# hbridge.net
KiCad netlist of a schematic drawn in Altium Designer
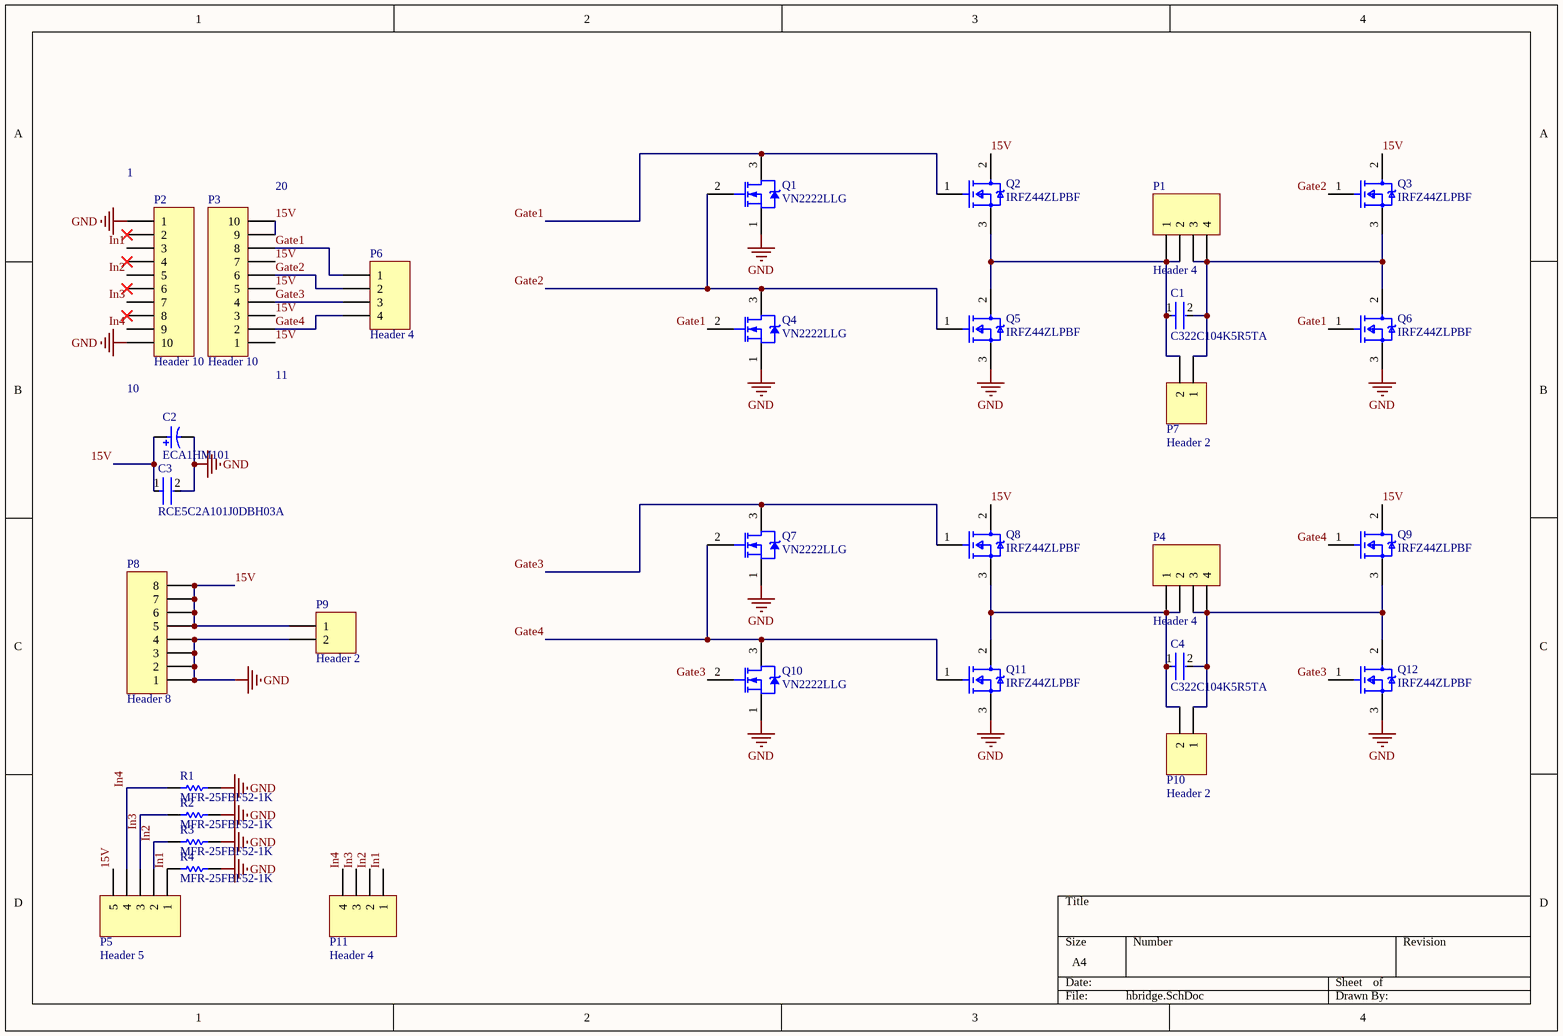
[diagram p0: hbridge.SchDoc]

(export (version "E")
  (design (tool "Eeschema 10.0.6"))
  (components
    (comp (ref "C1")
      (value "C322C104K5R5TA")
      (footprint "FP-C322C104K5R5TA-MFG")
      (description "CAP CER 0.1UF 50V X7R RADIAL")
      (fields (field (name "TOLERANCE") "10%") (field (name "VOLTAGE") "50V"))
      (libsource (lib "Altium Content Vault") (part "b4654b650e69147ec39a6b967a45e02"))
    )
    (comp (ref "C2")
      (value "ECA1HM101")
      (footprint "CAPPR65-350-1150X800X1250")
      (description "Aluminum Electrolytic Capacitor, 100 uF, +/- 20%, 50 V, -40 to 85 degC, 2-Pin THD, RoHS, Bulk")
      (fields (field (name "MANUFACTURER") "Panasonic") (field (name "VOLTAGE") "50V"))
      (libsource (lib "Altium Content Vault") (part "CAP-P-2"))
    )
    (comp (ref "C3")
      (value "RCE5C2A101J0DBH03A")
      (footprint "FP-RCE0DB-MFG")
      (description "Cap Ceramic 100pF 100V C0G ±5% Radial 2.5mm +125°C Ammo Pack")
      (fields (field (name "TOLERANCE") "5%"))
      (libsource (lib "Altium Content Vault") (part "b4654b650e69147ec39a6b967a45e02"))
    )
    (comp (ref "C4")
      (value "C322C104K5R5TA")
      (footprint "FP-C322C104K5R5TA-MFG")
      (description "CAP CER 0.1UF 50V X7R RADIAL")
      (fields (field (name "TOLERANCE") "10%") (field (name "VOLTAGE") "50V"))
      (libsource (lib "Altium Content Vault") (part "b4654b650e69147ec39a6b967a45e02"))
    )
    (comp (ref "P1")
      (value "Header 4")
      (footprint "HDR1X4")
      (description "Header, 4-Pin")
      (fields (field (name "PUBLISHER") "Altium Limited"))
      (libsource (lib "Miscellaneous Connectors") (part "Header 4"))
    )
    (comp (ref "P2")
      (value "Header 10")
      (footprint "HDR1X10")
      (description "Header, 10-Pin")
      (fields (field (name "PUBLISHER") "Altium Limited"))
      (libsource (lib "Miscellaneous Connectors") (part "Header 10"))
    )
    (comp (ref "P3")
      (value "Header 10")
      (footprint "HDR1X10")
      (description "Header, 10-Pin")
      (fields (field (name "PUBLISHER") "Altium Limited"))
      (libsource (lib "") (part "Header 10_1"))
    )
    (comp (ref "P4")
      (value "Header 4")
      (footprint "HDR1X4")
      (description "Header, 4-Pin")
      (fields (field (name "PUBLISHER") "Altium Limited"))
      (libsource (lib "Miscellaneous Connectors") (part "Header 4"))
    )
    (comp (ref "P5")
      (value "Header 5")
      (footprint "HDR1X5")
      (description "Header, 5-Pin")
      (fields (field (name "PUBLISHER") "Altium Limited"))
      (libsource (lib "Miscellaneous Connectors") (part "Header 5"))
    )
    (comp (ref "P6")
      (value "Header 4")
      (footprint "HDR1X4")
      (description "Header, 4-Pin")
      (fields (field (name "PUBLISHER") "Altium Limited"))
      (libsource (lib "") (part "Header 4_2"))
    )
    (comp (ref "P7")
      (value "Header 2")
      (footprint "HDR1X2")
      (description "Header, 2-Pin")
      (fields (field (name "PUBLISHER") "Altium Limited"))
      (libsource (lib "Miscellaneous Connectors") (part "Header 2"))
    )
    (comp (ref "P8")
      (value "Header 8")
      (footprint "HDR1X8")
      (description "Header, 8-Pin")
      (fields (field (name "PUBLISHER") "Altium Limited"))
      (libsource (lib "Miscellaneous Connectors") (part "Header 8"))
    )
    (comp (ref "P9")
      (value "Header 2")
      (footprint "HDR1X2")
      (description "Header, 2-Pin")
      (fields (field (name "PUBLISHER") "Altium Limited"))
      (libsource (lib "") (part "Header 2_1"))
    )
    (comp (ref "P10")
      (value "Header 2")
      (footprint "HDR1X2")
      (description "Header, 2-Pin")
      (fields (field (name "PUBLISHER") "Altium Limited"))
      (libsource (lib "Miscellaneous Connectors") (part "Header 2"))
    )
    (comp (ref "P11")
      (value "Header 4")
      (footprint "HDR1X4")
      (description "Header, 4-Pin")
      (fields (field (name "PUBLISHER") "Altium Limited"))
      (libsource (lib "") (part "Header 4_1"))
    )
    (comp (ref "Q1")
      (value "VN2222LLG")
      (footprint "ONSC-TO-92-3-29-11")
      (description "Small Signal MOSFET, 150 mA, 60 V, N-Channel, 3-Pin TO-92, Pb-Free, Bulk Box")
      (fields (field (name "MANUFACTURER") "On Semiconductor"))
      (libsource (lib "Altium Content Vault") (part "ONSC-NMOS-S1G2D3-3"))
    )
    (comp (ref "Q2")
      (value "IRFZ44ZLPBF")
      (footprint "FP-PG-TO262-3-MFG")
      (description "MOSFET N-CH 55V 51A TO262")
      (libsource (lib "Altium Content Vault") (part "b09f7f152735e370c1ea22a33fa83d6"))
    )
    (comp (ref "Q3")
      (value "IRFZ44ZLPBF")
      (footprint "FP-PG-TO262-3-MFG")
      (description "MOSFET N-CH 55V 51A TO262")
      (libsource (lib "Altium Content Vault") (part "b09f7f152735e370c1ea22a33fa83d6"))
    )
    (comp (ref "Q4")
      (value "VN2222LLG")
      (footprint "ONSC-TO-92-3-29-11")
      (description "Small Signal MOSFET, 150 mA, 60 V, N-Channel, 3-Pin TO-92, Pb-Free, Bulk Box")
      (fields (field (name "MANUFACTURER") "On Semiconductor"))
      (libsource (lib "Altium Content Vault") (part "ONSC-NMOS-S1G2D3-3"))
    )
    (comp (ref "Q5")
      (value "IRFZ44ZLPBF")
      (footprint "FP-PG-TO262-3-MFG")
      (description "MOSFET N-CH 55V 51A TO262")
      (libsource (lib "Altium Content Vault") (part "b09f7f152735e370c1ea22a33fa83d6"))
    )
    (comp (ref "Q6")
      (value "IRFZ44ZLPBF")
      (footprint "FP-PG-TO262-3-MFG")
      (description "MOSFET N-CH 55V 51A TO262")
      (libsource (lib "Altium Content Vault") (part "b09f7f152735e370c1ea22a33fa83d6"))
    )
    (comp (ref "Q7")
      (value "VN2222LLG")
      (footprint "ONSC-TO-92-3-29-11")
      (description "Small Signal MOSFET, 150 mA, 60 V, N-Channel, 3-Pin TO-92, Pb-Free, Bulk Box")
      (fields (field (name "MANUFACTURER") "On Semiconductor"))
      (libsource (lib "Altium Content Vault") (part "ONSC-NMOS-S1G2D3-3"))
    )
    (comp (ref "Q8")
      (value "IRFZ44ZLPBF")
      (footprint "FP-PG-TO262-3-MFG")
      (description "MOSFET N-CH 55V 51A TO262")
      (libsource (lib "Altium Content Vault") (part "b09f7f152735e370c1ea22a33fa83d6"))
    )
    (comp (ref "Q9")
      (value "IRFZ44ZLPBF")
      (footprint "FP-PG-TO262-3-MFG")
      (description "MOSFET N-CH 55V 51A TO262")
      (libsource (lib "Altium Content Vault") (part "b09f7f152735e370c1ea22a33fa83d6"))
    )
    (comp (ref "Q10")
      (value "VN2222LLG")
      (footprint "ONSC-TO-92-3-29-11")
      (description "Small Signal MOSFET, 150 mA, 60 V, N-Channel, 3-Pin TO-92, Pb-Free, Bulk Box")
      (fields (field (name "MANUFACTURER") "On Semiconductor"))
      (libsource (lib "Altium Content Vault") (part "ONSC-NMOS-S1G2D3-3"))
    )
    (comp (ref "Q11")
      (value "IRFZ44ZLPBF")
      (footprint "FP-PG-TO262-3-MFG")
      (description "MOSFET N-CH 55V 51A TO262")
      (libsource (lib "Altium Content Vault") (part "b09f7f152735e370c1ea22a33fa83d6"))
    )
    (comp (ref "Q12")
      (value "IRFZ44ZLPBF")
      (footprint "FP-PG-TO262-3-MFG")
      (description "MOSFET N-CH 55V 51A TO262")
      (libsource (lib "Altium Content Vault") (part "b09f7f152735e370c1ea22a33fa83d6"))
    )
    (comp (ref "R1")
      (value "MFR-25FBF52-1K")
      (footprint "RESA60-630X240")
      (description "Axial Resistor, 1 KOhm, +/- 1%, 250 mW, -55 to 155 degC, 2-Pin THD, RoHS, Bulk")
      (fields (field (name "TOLERANCE") "1%"))
      (libsource (lib "Altium Content Vault") (part "RES-2"))
    )
    (comp (ref "R2")
      (value "MFR-25FBF52-1K")
      (footprint "RESA60-630X240")
      (description "Axial Resistor, 1 KOhm, +/- 1%, 250 mW, -55 to 155 degC, 2-Pin THD, RoHS, Bulk")
      (fields (field (name "TOLERANCE") "1%"))
      (libsource (lib "Altium Content Vault") (part "RES-2"))
    )
    (comp (ref "R3")
      (value "MFR-25FBF52-1K")
      (footprint "RESA60-630X240")
      (description "Axial Resistor, 1 KOhm, +/- 1%, 250 mW, -55 to 155 degC, 2-Pin THD, RoHS, Bulk")
      (fields (field (name "TOLERANCE") "1%"))
      (libsource (lib "Altium Content Vault") (part "RES-2"))
    )
    (comp (ref "R4")
      (value "MFR-25FBF52-1K")
      (footprint "RESA60-630X240")
      (description "Axial Resistor, 1 KOhm, +/- 1%, 250 mW, -55 to 155 degC, 2-Pin THD, RoHS, Bulk")
      (fields (field (name "TOLERANCE") "1%"))
      (libsource (lib "Altium Content Vault") (part "RES-2"))
    )
  )
  (nets
    (net (code "1") (name "/15V") (class "Default")
      (node (ref "C2") (pin "1") (pinfunction "1_1") (pintype "passive"))
      (node (ref "C3") (pin "1") (pinfunction "1_1") (pintype "passive"))
      (node (ref "P3") (pin "1") (pinfunction "1_1") (pintype "passive"))
      (node (ref "P3") (pin "10") (pinfunction "10_10") (pintype "passive"))
      (node (ref "P3") (pin "3") (pinfunction "3_3") (pintype "passive"))
      (node (ref "P3") (pin "5") (pinfunction "5_5") (pintype "passive"))
      (node (ref "P3") (pin "7") (pinfunction "7_7") (pintype "passive"))
      (node (ref "P3") (pin "9") (pinfunction "9_9") (pintype "passive"))
      (node (ref "P5") (pin "5") (pinfunction "5_5") (pintype "passive"))
      (node (ref "P8") (pin "5") (pinfunction "5_5") (pintype "passive"))
      (node (ref "P8") (pin "6") (pinfunction "6_6") (pintype "passive"))
      (node (ref "P8") (pin "7") (pinfunction "7_7") (pintype "passive"))
      (node (ref "P8") (pin "8") (pinfunction "8_8") (pintype "passive"))
      (node (ref "P9") (pin "1") (pinfunction "1_1") (pintype "passive"))
      (node (ref "Q2") (pin "2") (pinfunction "D_2") (pintype "passive"))
      (node (ref "Q3") (pin "2") (pinfunction "D_2") (pintype "passive"))
      (node (ref "Q8") (pin "2") (pinfunction "D_2") (pintype "passive"))
      (node (ref "Q9") (pin "2") (pinfunction "D_2") (pintype "passive"))
    )
    (net (code "2") (name "/Gate1") (class "Default")
      (node (ref "P3") (pin "8") (pinfunction "8_8") (pintype "passive"))
      (node (ref "P6") (pin "1") (pinfunction "1_1") (pintype "passive"))
      (node (ref "Q1") (pin "3") (pinfunction "D_3") (pintype "passive"))
      (node (ref "Q2") (pin "1") (pinfunction "G_1") (pintype "passive"))
      (node (ref "Q4") (pin "2") (pinfunction "G_2") (pintype "passive"))
      (node (ref "Q6") (pin "1") (pinfunction "G_1") (pintype "passive"))
    )
    (net (code "3") (name "/Gate2") (class "Default")
      (node (ref "P3") (pin "6") (pinfunction "6_6") (pintype "passive"))
      (node (ref "P6") (pin "2") (pinfunction "2_2") (pintype "passive"))
      (node (ref "Q1") (pin "2") (pinfunction "G_2") (pintype "passive"))
      (node (ref "Q3") (pin "1") (pinfunction "G_1") (pintype "passive"))
      (node (ref "Q4") (pin "3") (pinfunction "D_3") (pintype "passive"))
      (node (ref "Q5") (pin "1") (pinfunction "G_1") (pintype "passive"))
    )
    (net (code "4") (name "/Gate3") (class "Default")
      (node (ref "P3") (pin "4") (pinfunction "4_4") (pintype "passive"))
      (node (ref "P6") (pin "3") (pinfunction "3_3") (pintype "passive"))
      (node (ref "Q10") (pin "2") (pinfunction "G_2") (pintype "passive"))
      (node (ref "Q12") (pin "1") (pinfunction "G_1") (pintype "passive"))
      (node (ref "Q7") (pin "3") (pinfunction "D_3") (pintype "passive"))
      (node (ref "Q8") (pin "1") (pinfunction "G_1") (pintype "passive"))
    )
    (net (code "5") (name "/Gate4") (class "Default")
      (node (ref "P3") (pin "2") (pinfunction "2_2") (pintype "passive"))
      (node (ref "P6") (pin "4") (pinfunction "4_4") (pintype "passive"))
      (node (ref "Q10") (pin "3") (pinfunction "D_3") (pintype "passive"))
      (node (ref "Q11") (pin "1") (pinfunction "G_1") (pintype "passive"))
      (node (ref "Q7") (pin "2") (pinfunction "G_2") (pintype "passive"))
      (node (ref "Q9") (pin "1") (pinfunction "G_1") (pintype "passive"))
    )
    (net (code "6") (name "/In1") (class "Default")
      (node (ref "P11") (pin "1") (pinfunction "1_1") (pintype "passive"))
      (node (ref "P2") (pin "3") (pinfunction "3_3") (pintype "passive"))
      (node (ref "P5") (pin "1") (pinfunction "1_1") (pintype "passive"))
      (node (ref "R4") (pin "2") (pinfunction "2_2") (pintype "passive"))
    )
    (net (code "7") (name "/In2") (class "Default")
      (node (ref "P11") (pin "2") (pinfunction "2_2") (pintype "passive"))
      (node (ref "P2") (pin "5") (pinfunction "5_5") (pintype "passive"))
      (node (ref "P5") (pin "2") (pinfunction "2_2") (pintype "passive"))
      (node (ref "R3") (pin "2") (pinfunction "2_2") (pintype "passive"))
    )
    (net (code "8") (name "/In3") (class "Default")
      (node (ref "P11") (pin "3") (pinfunction "3_3") (pintype "passive"))
      (node (ref "P2") (pin "7") (pinfunction "7_7") (pintype "passive"))
      (node (ref "P5") (pin "3") (pinfunction "3_3") (pintype "passive"))
      (node (ref "R2") (pin "2") (pinfunction "2_2") (pintype "passive"))
    )
    (net (code "9") (name "/In4") (class "Default")
      (node (ref "P11") (pin "4") (pinfunction "4_4") (pintype "passive"))
      (node (ref "P2") (pin "9") (pinfunction "9_9") (pintype "passive"))
      (node (ref "P5") (pin "4") (pinfunction "4_4") (pintype "passive"))
      (node (ref "R1") (pin "2") (pinfunction "2_2") (pintype "passive"))
    )
    (net (code "10") (name "GND") (class "Default")
      (node (ref "C2") (pin "2") (pinfunction "2_2") (pintype "passive"))
      (node (ref "C3") (pin "2") (pinfunction "2_2") (pintype "passive"))
      (node (ref "P2") (pin "1") (pinfunction "1_1") (pintype "passive"))
      (node (ref "P2") (pin "10") (pinfunction "10_10") (pintype "passive"))
      (node (ref "P8") (pin "1") (pinfunction "1_1") (pintype "passive"))
      (node (ref "P8") (pin "2") (pinfunction "2_2") (pintype "passive"))
      (node (ref "P8") (pin "3") (pinfunction "3_3") (pintype "passive"))
      (node (ref "P8") (pin "4") (pinfunction "4_4") (pintype "passive"))
      (node (ref "P9") (pin "2") (pinfunction "2_2") (pintype "passive"))
      (node (ref "Q1") (pin "1") (pinfunction "S_1") (pintype "passive"))
      (node (ref "Q10") (pin "1") (pinfunction "S_1") (pintype "passive"))
      (node (ref "Q11") (pin "3") (pinfunction "S_3") (pintype "passive"))
      (node (ref "Q12") (pin "3") (pinfunction "S_3") (pintype "passive"))
      (node (ref "Q4") (pin "1") (pinfunction "S_1") (pintype "passive"))
      (node (ref "Q5") (pin "3") (pinfunction "S_3") (pintype "passive"))
      (node (ref "Q6") (pin "3") (pinfunction "S_3") (pintype "passive"))
      (node (ref "Q7") (pin "1") (pinfunction "S_1") (pintype "passive"))
      (node (ref "R1") (pin "1") (pinfunction "1_1") (pintype "passive"))
      (node (ref "R2") (pin "1") (pinfunction "1_1") (pintype "passive"))
      (node (ref "R3") (pin "1") (pinfunction "1_1") (pintype "passive"))
      (node (ref "R4") (pin "1") (pinfunction "1_1") (pintype "passive"))
    )
    (net (code "11") (name "Net-(Q2-S)") (class "Default")
      (node (ref "C1") (pin "1") (pinfunction "1_1") (pintype "passive"))
      (node (ref "P1") (pin "1") (pinfunction "1_1") (pintype "passive"))
      (node (ref "P1") (pin "2") (pinfunction "2_2") (pintype "passive"))
      (node (ref "P7") (pin "2") (pinfunction "2_2") (pintype "passive"))
      (node (ref "Q2") (pin "3") (pinfunction "S_3") (pintype "passive"))
      (node (ref "Q5") (pin "2") (pinfunction "D_2") (pintype "passive"))
    )
    (net (code "12") (name "Net-(Q3-S)") (class "Default")
      (node (ref "C1") (pin "2") (pinfunction "2_2") (pintype "passive"))
      (node (ref "P1") (pin "3") (pinfunction "3_3") (pintype "passive"))
      (node (ref "P1") (pin "4") (pinfunction "4_4") (pintype "passive"))
      (node (ref "P7") (pin "1") (pinfunction "1_1") (pintype "passive"))
      (node (ref "Q3") (pin "3") (pinfunction "S_3") (pintype "passive"))
      (node (ref "Q6") (pin "2") (pinfunction "D_2") (pintype "passive"))
    )
    (net (code "13") (name "Net-(Q11-D)") (class "Default")
      (node (ref "C4") (pin "1") (pinfunction "1_1") (pintype "passive"))
      (node (ref "P10") (pin "2") (pinfunction "2_2") (pintype "passive"))
      (node (ref "P4") (pin "1") (pinfunction "1_1") (pintype "passive"))
      (node (ref "P4") (pin "2") (pinfunction "2_2") (pintype "passive"))
      (node (ref "Q11") (pin "2") (pinfunction "D_2") (pintype "passive"))
      (node (ref "Q8") (pin "3") (pinfunction "S_3") (pintype "passive"))
    )
    (net (code "14") (name "Net-(Q12-D)") (class "Default")
      (node (ref "C4") (pin "2") (pinfunction "2_2") (pintype "passive"))
      (node (ref "P10") (pin "1") (pinfunction "1_1") (pintype "passive"))
      (node (ref "P4") (pin "3") (pinfunction "3_3") (pintype "passive"))
      (node (ref "P4") (pin "4") (pinfunction "4_4") (pintype "passive"))
      (node (ref "Q12") (pin "2") (pinfunction "D_2") (pintype "passive"))
      (node (ref "Q9") (pin "3") (pinfunction "S_3") (pintype "passive"))
    )
    (net (code "15") (name "unconnected-(P2-Pad2)") (class "Default")
      (node (ref "P2") (pin "2") (pinfunction "2_2") (pintype "passive+no_connect"))
    )
    (net (code "16") (name "unconnected-(P2-Pad4)") (class "Default")
      (node (ref "P2") (pin "4") (pinfunction "4_4") (pintype "passive+no_connect"))
    )
    (net (code "17") (name "unconnected-(P2-Pad6)") (class "Default")
      (node (ref "P2") (pin "6") (pinfunction "6_6") (pintype "passive+no_connect"))
    )
    (net (code "18") (name "unconnected-(P2-Pad8)") (class "Default")
      (node (ref "P2") (pin "8") (pinfunction "8_8") (pintype "passive+no_connect"))
    )
  )
)
